# ParentBoardV2.net
KiCad netlist of a schematic drawn in Altium Designer
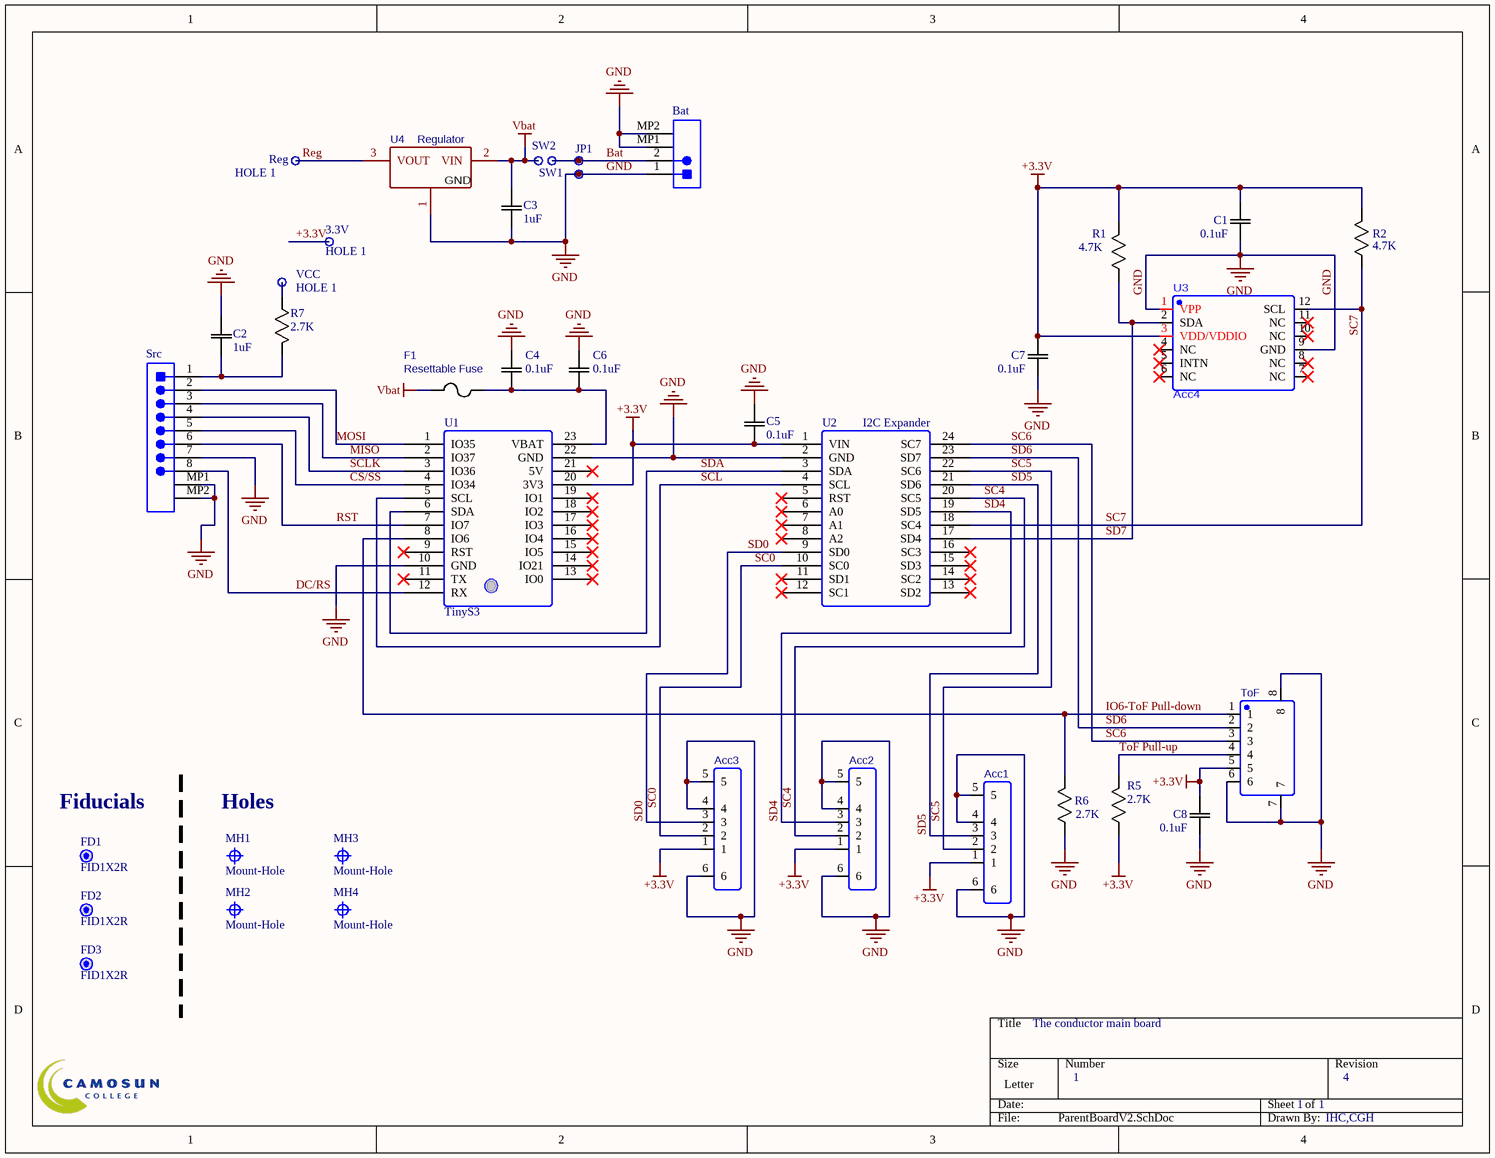
[diagram p0: ParentBoardV2.SchDoc]

(export (version "E")
  (design (tool "Eeschema 10.0.6"))
  (components
    (comp (ref "3.3V")
      (value "HOLE 1")
      (footprint "RAD0.1C")
      (libsource (lib "The conductor") (part "HOLE 1"))
    )
    (comp (ref "Acc1")
      (value "SM04B-SRSS")
      (footprint "CONN-SMD_4P-P1.00_SM04B-SRSS-TB-LF-SN")
      (description "4 pin JST connector")
      (fields
        (field (name "MANUFACTURER") "JST")
        (field (name "MANUFACTURER PART") "SM04B-SRSS-TB(LF)(SN)")
        (field (name "CONTRIBUTOR") "LCSC")
      )
      (libsource (lib "The conductor") (part "SM04B-SRSS-TB (LF)(SN)"))
    )
    (comp (ref "Acc2")
      (value "SM04B-SRSS")
      (footprint "CONN-SMD_4P-P1.00_SM04B-SRSS-TB-LF-SN")
      (description "4 pin JST connector")
      (fields
        (field (name "MANUFACTURER") "JST")
        (field (name "MANUFACTURER PART") "SM04B-SRSS-TB(LF)(SN)")
        (field (name "CONTRIBUTOR") "LCSC")
      )
      (libsource (lib "The conductor") (part "SM04B-SRSS-TB (LF)(SN)"))
    )
    (comp (ref "Acc3")
      (value "SM04B-SRSS")
      (footprint "CONN-SMD_4P-P1.00_SM04B-SRSS-TB-LF-SN")
      (description "4 pin JST connector")
      (fields
        (field (name "MANUFACTURER") "JST")
        (field (name "MANUFACTURER PART") "SM04B-SRSS-TB(LF)(SN)")
        (field (name "CONTRIBUTOR") "LCSC")
      )
      (libsource (lib "The conductor") (part "SM04B-SRSS-TB (LF)(SN)"))
    )
    (comp (ref "Bat")
      (value "CN-1P-2M-R2")
      (footprint "JST- S2B-PH-SM4-TB(LF)(SN)-2_V")
      (description "2 pin connector SMT 2 mm pitch")
      (fields (field (name "LCSC PART #") "C295747"))
      (libsource (lib "The conductor") (part "CN-1P-2M-R2"))
    )
    (comp (ref "C1")
      (value "0.1uF")
      (footprint "CAP_AMK107BJ475MK-T_TAY")
      (description "SMT Capacitor 0.1 uF")
      (fields
        (field (name "MANUFACTURER_PART_NUMBER") "AMK107BJ475MK-T")
        (field (name "LCSC PART #") "C1591")
        (field (name "COPYRIGHT") "Copyright (C) 2023 Ultra Librarian. All rights reserved.")
      )
      (libsource (lib "The conductor") (part "CL10B104KB8NNNC"))
    )
    (comp (ref "C2")
      (value "1uF")
      (footprint "CAP_AMK107BJ475MK-T_TAY")
      (description "SMT Capacitor 1 uF")
      (fields
        (field (name "MANUFACTURER_PART_NUMBER") "AMK107BJ475MK-T")
        (field (name "LCSC PART #") "C105524")
        (field (name "COPYRIGHT") "Copyright (C) 2023 Ultra Librarian. All rights reserved.")
      )
      (libsource (lib "The conductor") (part "CL10B105KQ8NNNC"))
    )
    (comp (ref "C3")
      (value "1uF")
      (footprint "CAP_AMK107BJ475MK-T_TAY")
      (description "SMT Capacitor 1 uF")
      (fields
        (field (name "MANUFACTURER_PART_NUMBER") "AMK107BJ475MK-T")
        (field (name "LCSC PART #") "C105524")
        (field (name "COPYRIGHT") "Copyright (C) 2023 Ultra Librarian. All rights reserved.")
      )
      (libsource (lib "The conductor") (part "CL10B105KQ8NNNC"))
    )
    (comp (ref "C4")
      (value "0.1uF")
      (footprint "CAP_AMK107BJ475MK-T_TAY")
      (description "SMT Capacitor 0.1 uF")
      (fields
        (field (name "MANUFACTURER_PART_NUMBER") "AMK107BJ475MK-T")
        (field (name "LCSC PART #") "C1591")
        (field (name "COPYRIGHT") "Copyright (C) 2023 Ultra Librarian. All rights reserved.")
      )
      (libsource (lib "The conductor") (part "CL10B104KB8NNNC"))
    )
    (comp (ref "C5")
      (value "0.1uF")
      (footprint "CAP_AMK107BJ475MK-T_TAY")
      (description "SMT Capacitor 0.1 uF")
      (fields
        (field (name "MANUFACTURER_PART_NUMBER") "AMK107BJ475MK-T")
        (field (name "LCSC PART #") "C1591")
        (field (name "COPYRIGHT") "Copyright (C) 2023 Ultra Librarian. All rights reserved.")
      )
      (libsource (lib "The conductor") (part "CL10B104KB8NNNC"))
    )
    (comp (ref "C6")
      (value "0.1uF")
      (footprint "CAP_AMK107BJ475MK-T_TAY")
      (description "SMT Capacitor 0.1 uF")
      (fields
        (field (name "MANUFACTURER_PART_NUMBER") "AMK107BJ475MK-T")
        (field (name "LCSC PART #") "C1591")
        (field (name "COPYRIGHT") "Copyright (C) 2023 Ultra Librarian. All rights reserved.")
      )
      (libsource (lib "The conductor") (part "CL10B104KB8NNNC"))
    )
    (comp (ref "C7")
      (value "0.1uF")
      (footprint "CAP_AMK107BJ475MK-T_TAY")
      (description "SMT Capacitor 0.1 uF")
      (fields
        (field (name "MANUFACTURER_PART_NUMBER") "AMK107BJ475MK-T")
        (field (name "LCSC PART #") "C1591")
        (field (name "COPYRIGHT") "Copyright (C) 2023 Ultra Librarian. All rights reserved.")
      )
      (libsource (lib "The conductor") (part "CL10B104KB8NNNC"))
    )
    (comp (ref "C8")
      (value "0.1uF")
      (footprint "CAP_AMK107BJ475MK-T_TAY")
      (description "SMT Capacitor 0.1 uF")
      (fields
        (field (name "MANUFACTURER_PART_NUMBER") "AMK107BJ475MK-T")
        (field (name "LCSC PART #") "C1591")
        (field (name "COPYRIGHT") "Copyright (C) 2023 Ultra Librarian. All rights reserved.")
      )
      (libsource (lib "The conductor") (part "CL10B104KB8NNNC"))
    )
    (comp (ref "F1")
      (value "Resettable Fuse")
      (footprint "F0805")
      (description "6V 350mA 100A 750mA 0805 Resettable Fuses ROHS")
      (fields
        (field (name "MANUFACTURER") "Littelfuse(美国力特)")
        (field (name "MANUFACTURER PART") "0805L035YR")
        (field (name "CONTRIBUTOR") "LCSC")
      )
      (libsource (lib "The conductor") (part "0805L035YR"))
    )
    (comp (ref "FD1")
      (value "FID1X2R")
      (footprint "Fiducial")
      (description "Fiducial - Round 1x2mm")
      (libsource (lib "The conductor") (part "FID1X2R"))
    )
    (comp (ref "FD2")
      (value "FID1X2R")
      (footprint "Fiducial")
      (description "Fiducial - Round 1x2mm")
      (libsource (lib "The conductor") (part "FID1X2R"))
    )
    (comp (ref "FD3")
      (value "FID1X2R")
      (footprint "Fiducial")
      (description "Fiducial - Round 1x2mm")
      (libsource (lib "The conductor") (part "FID1X2R"))
    )
    (comp (ref "JP1")
      (value "Battery")
      (footprint "RAD0.1")
      (libsource (lib "The conductor") (part "HOLE 2"))
    )
    (comp (ref "MH1")
      (value "Mount-Hole")
      (footprint "support 2 mm")
      (description "Mount hole")
      (fields (field (name "PUBLISHER") "Altium Limited"))
      (libsource (lib "The conductor") (part "MountHoles 2 mm"))
    )
    (comp (ref "MH2")
      (value "Mount-Hole")
      (footprint "support 2 mm")
      (description "Mount hole")
      (fields (field (name "PUBLISHER") "Altium Limited"))
      (libsource (lib "The conductor") (part "MountHoles 2 mm"))
    )
    (comp (ref "MH3")
      (value "Mount-Hole")
      (footprint "support 2 mm")
      (description "Mount hole")
      (fields (field (name "PUBLISHER") "Altium Limited"))
      (libsource (lib "The conductor") (part "MountHoles 2 mm"))
    )
    (comp (ref "MH4")
      (value "Mount-Hole")
      (footprint "support 2 mm")
      (description "Mount hole")
      (fields (field (name "PUBLISHER") "Altium Limited"))
      (libsource (lib "The conductor") (part "MountHoles 2 mm"))
    )
    (comp (ref "R1")
      (value "4.7K")
      (footprint "RC0603N_YAG")
      (description "SMT Resitor 4.7k")
      (fields
        (field (name "MANUFACTURER_PART_NUMBER") "RC0603JR-072K7L")
        (field (name "LCSC PART #") "C105428")
        (field (name "COPYRIGHT") "Copyright (C) 2023 Ultra Librarian. All rights reserved.")
      )
      (libsource (lib "The conductor") (part "RC0603JR-074K7L"))
    )
    (comp (ref "R2")
      (value "4.7K")
      (footprint "RC0603N_YAG")
      (description "SMT Resitor 4.7k")
      (fields
        (field (name "MANUFACTURER_PART_NUMBER") "RC0603JR-072K7L")
        (field (name "LCSC PART #") "C105428")
        (field (name "COPYRIGHT") "Copyright (C) 2023 Ultra Librarian. All rights reserved.")
      )
      (libsource (lib "The conductor") (part "RC0603JR-074K7L"))
    )
    (comp (ref "R5")
      (value "2.7K")
      (footprint "RC0603N_YAG")
      (description "SMT Resitor 2.7k")
      (fields
        (field (name "MANUFACTURER_PART_NUMBER") "RC0603JR-072K7L")
        (field (name "LCSC PART #") "C127451")
        (field (name "COPYRIGHT") "Copyright (C) 2023 Ultra Librarian. All rights reserved.")
      )
      (libsource (lib "The conductor") (part "RC0603JR-072K7L"))
    )
    (comp (ref "R6")
      (value "2.7K")
      (footprint "RC0603N_YAG")
      (description "SMT Resitor 2.7k")
      (fields
        (field (name "MANUFACTURER_PART_NUMBER") "RC0603JR-072K7L")
        (field (name "LCSC PART #") "C127451")
        (field (name "COPYRIGHT") "Copyright (C) 2023 Ultra Librarian. All rights reserved.")
      )
      (libsource (lib "The conductor") (part "RC0603JR-072K7L"))
    )
    (comp (ref "R7")
      (value "2.7K")
      (footprint "RC0603N_YAG")
      (description "SMT Resitor 2.7k")
      (fields
        (field (name "MANUFACTURER_PART_NUMBER") "RC0603JR-072K7L")
        (field (name "LCSC PART #") "C127451")
        (field (name "COPYRIGHT") "Copyright (C) 2023 Ultra Librarian. All rights reserved.")
      )
      (libsource (lib "The conductor") (part "RC0603JR-072K7L"))
    )
    (comp (ref "Reg")
      (value "HOLE 1")
      (footprint "RAD0.1C")
      (libsource (lib "The conductor") (part "HOLE 1"))
    )
    (comp (ref "Src")
      (value "SM08B-SRSS-TB(LF)(SN)")
      (footprint "JST-SM08B-SRSS-TB_V")
      (description "Male Header, Pitch 1 mm, 1 x 8 Position, Height 2.95 mm, -25 to 85 degC, RoHS, Tape and Reel")
      (fields (field (name "MANUFACTURER") "JST") (field (name "LCSC PART #") "C160407"))
      (libsource (lib "The conductor") (part "CMP-2000-07082-1"))
    )
    (comp (ref "SW1")
      (value "HOLE 1")
      (footprint "RAD0.1C")
      (libsource (lib "The conductor") (part "HOLE 1"))
    )
    (comp (ref "SW2")
      (value "HOLE 1")
      (footprint "RAD0.1C")
      (libsource (lib "The conductor") (part "HOLE 1"))
    )
    (comp (ref "ToF")
      (value "ToF sensor connector")
      (footprint "CONN-SMD_SM06B-SRSS-TB-LF-SN")
      (description "6 pin connector")
      (fields
        (field (name "MANUFACTURER") "JST")
        (field (name "MANUFACTURER PART") "SM06B-SRSS-TB(LF)(SN)")
        (field (name "CONTRIBUTOR") "LCSC")
      )
      (libsource (lib "The conductor") (part "SM06B-SRSS-TB(LF)(SN)"))
    )
    (comp (ref "U1")
      (value "TinyS3")
      (footprint "TinyS3")
      (description "TinyS3_1")
      (libsource (lib "The conductor") (part "TinyS3_1"))
    )
    (comp (ref "U2")
      (value "I2C Expander")
      (footprint "MODULE_2717")
      (libsource (lib "The conductor") (part "I2C Expander"))
    )
    (comp (ref "U3")
      (value "Acc4")
      (footprint "LGA-12_L2.0-W2.0-P0.50-BL")
      (description "VLGA-12 Attitude Sensor/Gyroscope ROHS")
      (fields (field (name "LCSC PART #") "MC3416-P"))
      (libsource (lib "The conductor") (part "MC3416-P"))
    )
    (comp (ref "U4")
      (value "Regulator")
      (footprint "SOT89-150P350X160-3N")
      (description "Fixed 24V 3.3V 1.5V @ 150mA SOT-89-3 Linear Voltage Regulators (LDO) RoHS")
      (fields
        (field (name "MANUFACTURER") "DIODES(美台)")
        (field (name "MANUFACTURER PART") "AP7380-33Y-13")
        (field (name "CONTRIBUTOR") "LCSC")
      )
      (libsource (lib "The conductor") (part "AP7380-33Y-13"))
    )
    (comp (ref "VCC")
      (value "HOLE 1")
      (footprint "RAD0.1C")
      (libsource (lib "The conductor") (part "HOLE 1"))
    )
  )
  (nets
    (net (code "1") (name "+3.3V") (class "Default")
      (node (ref "3.3V") (pin "1") (pinfunction "1_1") (pintype "passive"))
      (node (ref "Acc1") (pin "1") (pinfunction "1_1") (pintype "passive"))
      (node (ref "Acc2") (pin "1") (pinfunction "1_1") (pintype "passive"))
      (node (ref "Acc3") (pin "1") (pinfunction "1_1") (pintype "passive"))
      (node (ref "C1") (pin "2") (pinfunction "2_2") (pintype "passive"))
      (node (ref "C5") (pin "1") (pinfunction "1_1") (pintype "passive"))
      (node (ref "C7") (pin "2") (pinfunction "2_2") (pintype "passive"))
      (node (ref "C8") (pin "2") (pinfunction "2_2") (pintype "passive"))
      (node (ref "R1") (pin "1") (pinfunction "1_1") (pintype "passive"))
      (node (ref "R2") (pin "1") (pinfunction "1_1") (pintype "passive"))
      (node (ref "R5") (pin "2") (pinfunction "2_2") (pintype "passive"))
      (node (ref "ToF") (pin "5") (pinfunction "5_5") (pintype "passive"))
      (node (ref "U1") (pin "20") (pinfunction "3V3_20") (pintype "passive"))
      (node (ref "U2") (pin "1") (pinfunction "VIN_1") (pintype "passive"))
      (node (ref "U3") (pin "3") (pinfunction "VDD/VDDIO_3") (pintype "passive"))
    )
    (net (code "2") (name "/Bat") (class "Default")
      (node (ref "Bat") (pin "2") (pinfunction "2_2") (pintype "passive"))
      (node (ref "JP1") (pin "2") (pinfunction "2_2") (pintype "passive"))
      (node (ref "SW1") (pin "1") (pinfunction "1_1") (pintype "passive"))
    )
    (net (code "3") (name "/CS{slash}SS") (class "Default")
      (node (ref "Src") (pin "5") (pinfunction "5_5") (pintype "passive"))
      (node (ref "U1") (pin "4") (pinfunction "IO34_4") (pintype "passive"))
    )
    (net (code "4") (name "/DC{slash}RS") (class "Default")
      (node (ref "Src") (pin "8") (pinfunction "8_8") (pintype "passive"))
      (node (ref "U1") (pin "12") (pinfunction "RX_12") (pintype "passive"))
    )
    (net (code "5") (name "/IO6-ToF Pull-down") (class "Default")
      (node (ref "R6") (pin "1") (pinfunction "1_1") (pintype "passive"))
      (node (ref "ToF") (pin "1") (pinfunction "1_1") (pintype "passive"))
      (node (ref "U1") (pin "8") (pinfunction "IO6_8") (pintype "passive"))
    )
    (net (code "6") (name "/MISO") (class "Default")
      (node (ref "Src") (pin "3") (pinfunction "3_3") (pintype "passive"))
      (node (ref "U1") (pin "2") (pinfunction "IO37_2") (pintype "passive"))
    )
    (net (code "7") (name "/MOSI") (class "Default")
      (node (ref "Src") (pin "2") (pinfunction "2_2") (pintype "passive"))
      (node (ref "U1") (pin "1") (pinfunction "IO35_1") (pintype "passive"))
    )
    (net (code "8") (name "/RST") (class "Default")
      (node (ref "Src") (pin "6") (pinfunction "6_6") (pintype "passive"))
      (node (ref "U1") (pin "7") (pinfunction "IO7_7") (pintype "passive"))
    )
    (net (code "9") (name "/Reg") (class "Default")
      (node (ref "Reg") (pin "1") (pinfunction "1_1") (pintype "passive"))
      (node (ref "U4") (pin "3") (pinfunction "VOUT_3") (pintype "passive"))
    )
    (net (code "10") (name "/SC0") (class "Default")
      (node (ref "Acc3") (pin "2") (pinfunction "2_2") (pintype "passive"))
      (node (ref "U2") (pin "10") (pinfunction "SC0_10") (pintype "passive"))
    )
    (net (code "11") (name "/SC4") (class "Default")
      (node (ref "Acc2") (pin "2") (pinfunction "2_2") (pintype "passive"))
      (node (ref "U2") (pin "20") (pinfunction "SC5_20") (pintype "passive"))
    )
    (net (code "12") (name "/SC5") (class "Default")
      (node (ref "Acc1") (pin "2") (pinfunction "2_2") (pintype "passive"))
      (node (ref "U2") (pin "22") (pinfunction "SC6_22") (pintype "passive"))
    )
    (net (code "13") (name "/SC6") (class "Default")
      (node (ref "ToF") (pin "3") (pinfunction "3_3") (pintype "passive"))
      (node (ref "U2") (pin "24") (pinfunction "SC7_24") (pintype "passive"))
    )
    (net (code "14") (name "/SC7") (class "Default")
      (node (ref "R2") (pin "2") (pinfunction "2_2") (pintype "passive"))
      (node (ref "U2") (pin "18") (pinfunction "SC4_18") (pintype "passive"))
      (node (ref "U3") (pin "12") (pinfunction "SCL_12") (pintype "passive"))
    )
    (net (code "15") (name "/SCL") (class "Default")
      (node (ref "U1") (pin "5") (pinfunction "SCL_5") (pintype "passive"))
      (node (ref "U2") (pin "4") (pinfunction "SCL_4") (pintype "passive"))
    )
    (net (code "16") (name "/SCLK") (class "Default")
      (node (ref "Src") (pin "4") (pinfunction "4_4") (pintype "passive"))
      (node (ref "U1") (pin "3") (pinfunction "IO36_3") (pintype "passive"))
    )
    (net (code "17") (name "/SD0") (class "Default")
      (node (ref "Acc3") (pin "3") (pinfunction "3_3") (pintype "passive"))
      (node (ref "U2") (pin "9") (pinfunction "SD0_9") (pintype "passive"))
    )
    (net (code "18") (name "/SD4") (class "Default")
      (node (ref "Acc2") (pin "3") (pinfunction "3_3") (pintype "passive"))
      (node (ref "U2") (pin "19") (pinfunction "SD5_19") (pintype "passive"))
    )
    (net (code "19") (name "/SD5") (class "Default")
      (node (ref "Acc1") (pin "3") (pinfunction "3_3") (pintype "passive"))
      (node (ref "U2") (pin "21") (pinfunction "SD6_21") (pintype "passive"))
    )
    (net (code "20") (name "/SD6") (class "Default")
      (node (ref "ToF") (pin "2") (pinfunction "2_2") (pintype "passive"))
      (node (ref "U2") (pin "23") (pinfunction "SD7_23") (pintype "passive"))
    )
    (net (code "21") (name "/SD7") (class "Default")
      (node (ref "R1") (pin "2") (pinfunction "2_2") (pintype "passive"))
      (node (ref "U2") (pin "17") (pinfunction "SD4_17") (pintype "passive"))
      (node (ref "U3") (pin "2") (pinfunction "SDA_2") (pintype "passive"))
    )
    (net (code "22") (name "/SDA") (class "Default")
      (node (ref "U1") (pin "6") (pinfunction "SDA_6") (pintype "passive"))
      (node (ref "U2") (pin "3") (pinfunction "SDA_3") (pintype "passive"))
    )
    (net (code "23") (name "/ToF Pull-up") (class "Default")
      (node (ref "R5") (pin "1") (pinfunction "1_1") (pintype "passive"))
      (node (ref "ToF") (pin "4") (pinfunction "4_4") (pintype "passive"))
    )
    (net (code "24") (name "GND") (class "Default")
      (node (ref "Acc1") (pin "4") (pinfunction "4_4") (pintype "passive"))
      (node (ref "Acc1") (pin "5") (pinfunction "5_5") (pintype "passive"))
      (node (ref "Acc1") (pin "6") (pinfunction "6_6") (pintype "passive"))
      (node (ref "Acc2") (pin "4") (pinfunction "4_4") (pintype "passive"))
      (node (ref "Acc2") (pin "5") (pinfunction "5_5") (pintype "passive"))
      (node (ref "Acc2") (pin "6") (pinfunction "6_6") (pintype "passive"))
      (node (ref "Acc3") (pin "4") (pinfunction "4_4") (pintype "passive"))
      (node (ref "Acc3") (pin "5") (pinfunction "5_5") (pintype "passive"))
      (node (ref "Acc3") (pin "6") (pinfunction "6_6") (pintype "passive"))
      (node (ref "Bat") (pin "1") (pinfunction "1_1") (pintype "passive"))
      (node (ref "Bat") (pin "MP1") (pinfunction "MP1_MP1") (pintype "passive"))
      (node (ref "Bat") (pin "MP2") (pinfunction "MP2_MP2") (pintype "passive"))
      (node (ref "C1") (pin "1") (pinfunction "1_1") (pintype "passive"))
      (node (ref "C2") (pin "2") (pinfunction "2_2") (pintype "passive"))
      (node (ref "C3") (pin "1") (pinfunction "1_1") (pintype "passive"))
      (node (ref "C4") (pin "2") (pinfunction "2_2") (pintype "passive"))
      (node (ref "C5") (pin "2") (pinfunction "2_2") (pintype "passive"))
      (node (ref "C6") (pin "2") (pinfunction "2_2") (pintype "passive"))
      (node (ref "C7") (pin "1") (pinfunction "1_1") (pintype "passive"))
      (node (ref "C8") (pin "1") (pinfunction "1_1") (pintype "passive"))
      (node (ref "JP1") (pin "1") (pinfunction "1_1") (pintype "passive"))
      (node (ref "R6") (pin "2") (pinfunction "2_2") (pintype "passive"))
      (node (ref "Src") (pin "7") (pinfunction "7_7") (pintype "passive"))
      (node (ref "Src") (pin "MP1") (pinfunction "MP1_MP1") (pintype "passive"))
      (node (ref "Src") (pin "MP2") (pinfunction "MP2_MP2") (pintype "passive"))
      (node (ref "ToF") (pin "6") (pinfunction "6_6") (pintype "passive"))
      (node (ref "ToF") (pin "7") (pinfunction "7_7") (pintype "passive"))
      (node (ref "ToF") (pin "8") (pinfunction "8_8") (pintype "passive"))
      (node (ref "U1") (pin "10") (pinfunction "GND_10") (pintype "passive"))
      (node (ref "U1") (pin "22") (pinfunction "GND_22") (pintype "passive"))
      (node (ref "U2") (pin "2") (pinfunction "GND_2") (pintype "passive"))
      (node (ref "U3") (pin "1") (pinfunction "VPP_1") (pintype "passive"))
      (node (ref "U3") (pin "9") (pinfunction "GND_9") (pintype "passive"))
      (node (ref "U4") (pin "1") (pinfunction "GND_1") (pintype "passive"))
    )
    (net (code "25") (name "Net-(C2-Pad1)") (class "Default")
      (node (ref "C2") (pin "1") (pinfunction "1_1") (pintype "passive"))
      (node (ref "R7") (pin "1") (pinfunction "1_1") (pintype "passive"))
      (node (ref "Src") (pin "1") (pinfunction "1_1") (pintype "passive"))
    )
    (net (code "26") (name "Net-(R7-Pad2)") (class "Default")
      (node (ref "R7") (pin "2") (pinfunction "2_2") (pintype "passive"))
      (node (ref "VCC") (pin "1") (pinfunction "1_1") (pintype "passive"))
    )
    (net (code "27") (name "Net-(U1-VBAT)") (class "Default")
      (node (ref "C4") (pin "1") (pinfunction "1_1") (pintype "passive"))
      (node (ref "C6") (pin "1") (pinfunction "1_1") (pintype "passive"))
      (node (ref "F1") (pin "1") (pinfunction "1_1") (pintype "passive"))
      (node (ref "U1") (pin "23") (pinfunction "VBAT_23") (pintype "passive"))
    )
    (net (code "28") (name "Vbat") (class "Default")
      (node (ref "C3") (pin "2") (pinfunction "2_2") (pintype "passive"))
      (node (ref "F1") (pin "2") (pinfunction "2_2") (pintype "passive"))
      (node (ref "SW2") (pin "1") (pinfunction "1_1") (pintype "passive"))
      (node (ref "U4") (pin "2") (pinfunction "VIN_2") (pintype "passive"))
    )
    (net (code "29") (name "unconnected-(U1-5V-Pad21)") (class "Default")
      (node (ref "U1") (pin "21") (pinfunction "5V_21") (pintype "passive+no_connect"))
    )
    (net (code "30") (name "unconnected-(U1-IO0-Pad13)") (class "Default")
      (node (ref "U1") (pin "13") (pinfunction "IO0_13") (pintype "passive+no_connect"))
    )
    (net (code "31") (name "unconnected-(U1-IO1-Pad19)") (class "Default")
      (node (ref "U1") (pin "19") (pinfunction "IO1_19") (pintype "passive+no_connect"))
    )
    (net (code "32") (name "unconnected-(U1-IO2-Pad18)") (class "Default")
      (node (ref "U1") (pin "18") (pinfunction "IO2_18") (pintype "passive+no_connect"))
    )
    (net (code "33") (name "unconnected-(U1-IO3-Pad17)") (class "Default")
      (node (ref "U1") (pin "17") (pinfunction "IO3_17") (pintype "passive+no_connect"))
    )
    (net (code "34") (name "unconnected-(U1-IO4-Pad16)") (class "Default")
      (node (ref "U1") (pin "16") (pinfunction "IO4_16") (pintype "passive+no_connect"))
    )
    (net (code "35") (name "unconnected-(U1-IO5-Pad15)") (class "Default")
      (node (ref "U1") (pin "15") (pinfunction "IO5_15") (pintype "passive+no_connect"))
    )
    (net (code "36") (name "unconnected-(U1-IO21-Pad14)") (class "Default")
      (node (ref "U1") (pin "14") (pinfunction "IO21_14") (pintype "passive+no_connect"))
    )
    (net (code "37") (name "unconnected-(U1-RST-Pad9)") (class "Default")
      (node (ref "U1") (pin "9") (pinfunction "RST_9") (pintype "passive+no_connect"))
    )
    (net (code "38") (name "unconnected-(U1-TX-Pad11)") (class "Default")
      (node (ref "U1") (pin "11") (pinfunction "TX_11") (pintype "passive+no_connect"))
    )
    (net (code "39") (name "unconnected-(U2-A0-Pad6)") (class "Default")
      (node (ref "U2") (pin "6") (pinfunction "A0_6") (pintype "passive+no_connect"))
    )
    (net (code "40") (name "unconnected-(U2-A1-Pad7)") (class "Default")
      (node (ref "U2") (pin "7") (pinfunction "A1_7") (pintype "passive+no_connect"))
    )
    (net (code "41") (name "unconnected-(U2-A2-Pad8)") (class "Default")
      (node (ref "U2") (pin "8") (pinfunction "A2_8") (pintype "passive+no_connect"))
    )
    (net (code "42") (name "unconnected-(U2-RST-Pad5)") (class "Default")
      (node (ref "U2") (pin "5") (pinfunction "RST_5") (pintype "passive+no_connect"))
    )
    (net (code "43") (name "unconnected-(U2-SC1-Pad12)") (class "Default")
      (node (ref "U2") (pin "12") (pinfunction "SC1_12") (pintype "passive+no_connect"))
    )
    (net (code "44") (name "unconnected-(U2-SC2-Pad14)") (class "Default")
      (node (ref "U2") (pin "14") (pinfunction "SC2_14") (pintype "passive+no_connect"))
    )
    (net (code "45") (name "unconnected-(U2-SC3-Pad16)") (class "Default")
      (node (ref "U2") (pin "16") (pinfunction "SC3_16") (pintype "passive+no_connect"))
    )
    (net (code "46") (name "unconnected-(U2-SD1-Pad11)") (class "Default")
      (node (ref "U2") (pin "11") (pinfunction "SD1_11") (pintype "passive+no_connect"))
    )
    (net (code "47") (name "unconnected-(U2-SD2-Pad13)") (class "Default")
      (node (ref "U2") (pin "13") (pinfunction "SD2_13") (pintype "passive+no_connect"))
    )
    (net (code "48") (name "unconnected-(U2-SD3-Pad15)") (class "Default")
      (node (ref "U2") (pin "15") (pinfunction "SD3_15") (pintype "passive+no_connect"))
    )
    (net (code "49") (name "unconnected-(U3-INTN-Pad5)") (class "Default")
      (node (ref "U3") (pin "5") (pinfunction "INTN_5") (pintype "passive+no_connect"))
    )
    (net (code "50") (name "unconnected-(U3-NC-Pad4)") (class "Default")
      (node (ref "U3") (pin "4") (pinfunction "NC_4") (pintype "passive+no_connect"))
    )
    (net (code "51") (name "unconnected-(U3-NC-Pad6)") (class "Default")
      (node (ref "U3") (pin "6") (pinfunction "NC_6") (pintype "passive+no_connect"))
    )
    (net (code "52") (name "unconnected-(U3-NC-Pad7)") (class "Default")
      (node (ref "U3") (pin "7") (pinfunction "NC_7") (pintype "passive+no_connect"))
    )
    (net (code "53") (name "unconnected-(U3-NC-Pad8)") (class "Default")
      (node (ref "U3") (pin "8") (pinfunction "NC_8") (pintype "passive+no_connect"))
    )
    (net (code "54") (name "unconnected-(U3-NC-Pad10)") (class "Default")
      (node (ref "U3") (pin "10") (pinfunction "NC_10") (pintype "passive+no_connect"))
    )
    (net (code "55") (name "unconnected-(U3-NC-Pad11)") (class "Default")
      (node (ref "U3") (pin "11") (pinfunction "NC_11") (pintype "passive+no_connect"))
    )
  )
)
